# LocalR1_0.net
KiCad netlist of a schematic drawn in EAGLE
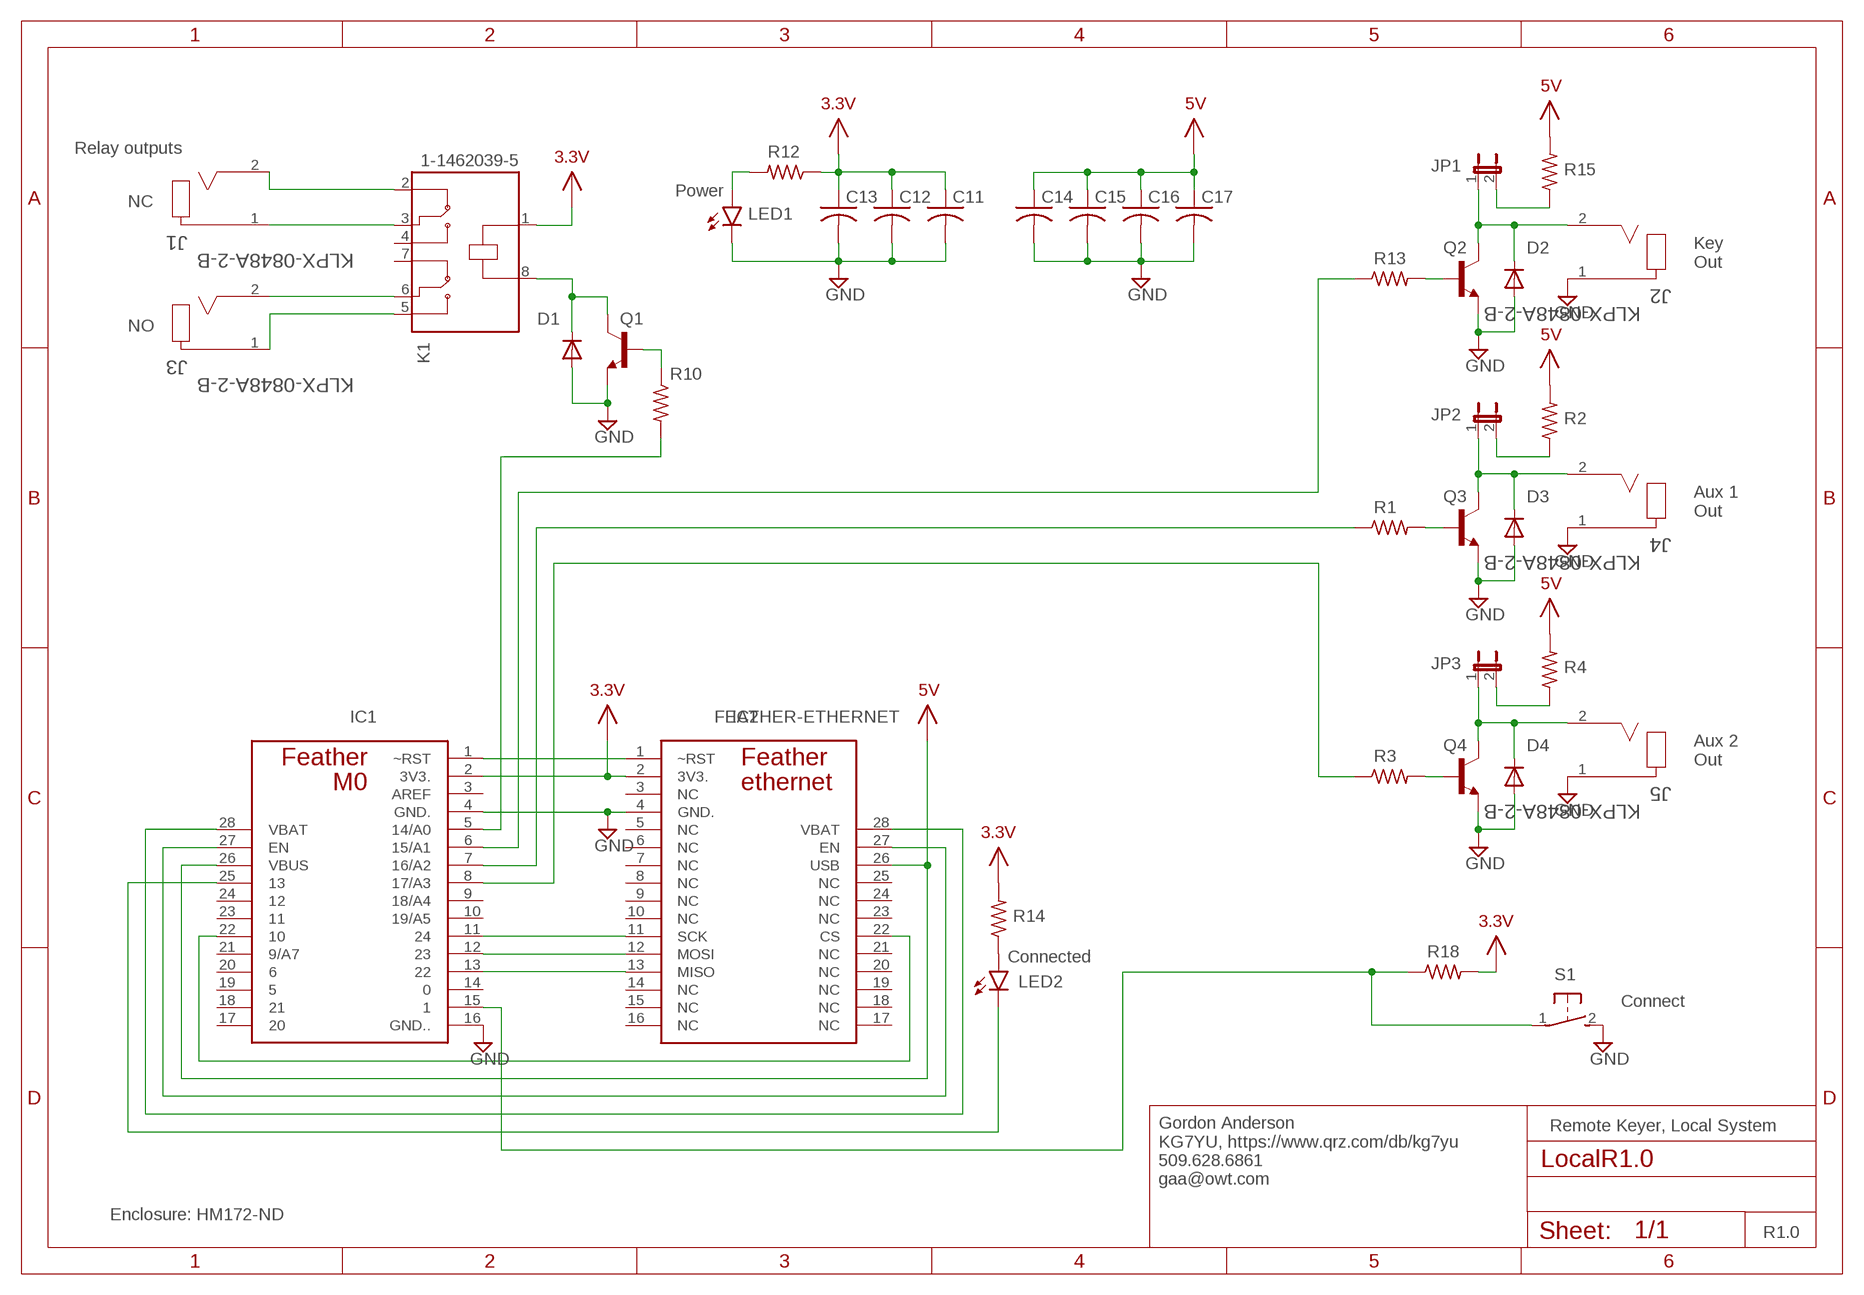
[diagram p0: schematic, sheet 1]

(export (version "E")
  (design (tool "Eeschema 10.0.6"))
  (components
    (comp (ref "C11")
      (value "C-USC0805")
      (footprint "eagle-import:C0805")
      (libsource (lib "eagle-import") (part "C-USC0805"))
    )
    (comp (ref "C12")
      (value "C-USC0805")
      (footprint "eagle-import:C0805")
      (libsource (lib "eagle-import") (part "C-USC0805"))
    )
    (comp (ref "C13")
      (value "C-USC0805")
      (footprint "eagle-import:C0805")
      (libsource (lib "eagle-import") (part "C-USC0805"))
    )
    (comp (ref "C14")
      (value "C-USC0805")
      (footprint "eagle-import:C0805")
      (libsource (lib "eagle-import") (part "C-USC0805"))
    )
    (comp (ref "C15")
      (value "C-USC0805")
      (footprint "eagle-import:C0805")
      (libsource (lib "eagle-import") (part "C-USC0805"))
    )
    (comp (ref "C16")
      (value "C-USC0805")
      (footprint "eagle-import:C0805")
      (libsource (lib "eagle-import") (part "C-USC0805"))
    )
    (comp (ref "C17")
      (value "C-USC0805")
      (footprint "eagle-import:C0805")
      (libsource (lib "eagle-import") (part "C-USC0805"))
    )
    (comp (ref "D1")
      (value "DIODE-SOD323-R")
      (footprint "eagle-import:SOD323-R")
      (libsource (lib "eagle-import") (part "DIODE-SOD323-R"))
    )
    (comp (ref "D2")
      (value "DIODE-SOD323-R")
      (footprint "eagle-import:SOD323-R")
      (libsource (lib "eagle-import") (part "DIODE-SOD323-R"))
    )
    (comp (ref "D3")
      (value "DIODE-SOD323-R")
      (footprint "eagle-import:SOD323-R")
      (libsource (lib "eagle-import") (part "DIODE-SOD323-R"))
    )
    (comp (ref "D4")
      (value "DIODE-SOD323-R")
      (footprint "eagle-import:SOD323-R")
      (libsource (lib "eagle-import") (part "DIODE-SOD323-R"))
    )
    (comp (ref "IC1")
      (value "FEATHER-M0")
      (footprint "eagle-import:FEATHER-M0")
      (libsource (lib "eagle-import") (part "FEATHER-M0"))
    )
    (comp (ref "IC2")
      (value "FEATHER-ETHERNET")
      (footprint "eagle-import:FEATHER-ETHERNET")
      (libsource (lib "eagle-import") (part "FEATHER-ETHERNET"))
    )
    (comp (ref "J1")
      (value "KLPX-0848A-2-B")
      (footprint "eagle-import:KLPX-0848A-2-B_KYC")
      (fields (field (name "COPYRIGHT") "Copyright (C) 2021 Ultra Librarian. All rights reserved."))
      (libsource (lib "eagle-import") (part "KLPX-0848A-2-B"))
    )
    (comp (ref "J2")
      (value "KLPX-0848A-2-B")
      (footprint "eagle-import:KLPX-0848A-2-B_KYC")
      (fields (field (name "COPYRIGHT") "Copyright (C) 2021 Ultra Librarian. All rights reserved."))
      (libsource (lib "eagle-import") (part "KLPX-0848A-2-B"))
    )
    (comp (ref "J3")
      (value "KLPX-0848A-2-B")
      (footprint "eagle-import:KLPX-0848A-2-B_KYC")
      (fields (field (name "COPYRIGHT") "Copyright (C) 2021 Ultra Librarian. All rights reserved."))
      (libsource (lib "eagle-import") (part "KLPX-0848A-2-B"))
    )
    (comp (ref "J4")
      (value "KLPX-0848A-2-B")
      (footprint "eagle-import:KLPX-0848A-2-B_KYC")
      (fields (field (name "COPYRIGHT") "Copyright (C) 2021 Ultra Librarian. All rights reserved."))
      (libsource (lib "eagle-import") (part "KLPX-0848A-2-B"))
    )
    (comp (ref "J5")
      (value "KLPX-0848A-2-B")
      (footprint "eagle-import:KLPX-0848A-2-B_KYC")
      (fields (field (name "COPYRIGHT") "Copyright (C) 2021 Ultra Librarian. All rights reserved."))
      (libsource (lib "eagle-import") (part "KLPX-0848A-2-B"))
    )
    (comp (ref "JP1")
      (value "JP1E")
      (footprint "eagle-import:JP1")
      (libsource (lib "eagle-import") (part "JP1E"))
    )
    (comp (ref "JP2")
      (value "JP1E")
      (footprint "eagle-import:JP1")
      (libsource (lib "eagle-import") (part "JP1E"))
    )
    (comp (ref "JP3")
      (value "JP1E")
      (footprint "eagle-import:JP1")
      (libsource (lib "eagle-import") (part "JP1E"))
    )
    (comp (ref "K1")
      (value "1-1462039-5")
      (footprint "eagle-import:RELAY_1-1462039-5")
      (fields (field (name "DIGI-KEY_PART_NUMBER") "PB1167-ND") (field (name "MF") "TE Connectivity"))
      (libsource (lib "eagle-import") (part "1-1462039-5"))
    )
    (comp (ref "LED1")
      (value "LED5MM")
      (footprint "eagle-import:LED5MM")
      (libsource (lib "eagle-import") (part "LED5MM"))
    )
    (comp (ref "LED2")
      (value "LED5MM")
      (footprint "eagle-import:LED5MM")
      (libsource (lib "eagle-import") (part "LED5MM"))
    )
    (comp (ref "Q1")
      (value "MMBT2369LT1-NPN-SOT23-BEC")
      (footprint "eagle-import:SOT23-BEC")
      (libsource (lib "eagle-import") (part "-NPN-SOT23-BECMMBT2369LT1"))
    )
    (comp (ref "Q2")
      (value "MMBT2369LT1-NPN-SOT23-BEC")
      (footprint "eagle-import:SOT23-BEC")
      (libsource (lib "eagle-import") (part "-NPN-SOT23-BECMMBT2369LT1"))
    )
    (comp (ref "Q3")
      (value "MMBT2369LT1-NPN-SOT23-BEC")
      (footprint "eagle-import:SOT23-BEC")
      (libsource (lib "eagle-import") (part "-NPN-SOT23-BECMMBT2369LT1"))
    )
    (comp (ref "Q4")
      (value "MMBT2369LT1-NPN-SOT23-BEC")
      (footprint "eagle-import:SOT23-BEC")
      (libsource (lib "eagle-import") (part "-NPN-SOT23-BECMMBT2369LT1"))
    )
    (comp (ref "R1")
      (value "R-US_R0805")
      (footprint "eagle-import:R0805")
      (libsource (lib "eagle-import") (part "R-US_R0805"))
    )
    (comp (ref "R2")
      (value "R-US_R0805")
      (footprint "eagle-import:R0805")
      (libsource (lib "eagle-import") (part "R-US_R0805"))
    )
    (comp (ref "R3")
      (value "R-US_R0805")
      (footprint "eagle-import:R0805")
      (libsource (lib "eagle-import") (part "R-US_R0805"))
    )
    (comp (ref "R4")
      (value "R-US_R0805")
      (footprint "eagle-import:R0805")
      (libsource (lib "eagle-import") (part "R-US_R0805"))
    )
    (comp (ref "R10")
      (value "R-US_R0805")
      (footprint "eagle-import:R0805")
      (libsource (lib "eagle-import") (part "R-US_R0805"))
    )
    (comp (ref "R12")
      (value "R-US_R0805")
      (footprint "eagle-import:R0805")
      (libsource (lib "eagle-import") (part "R-US_R0805"))
    )
    (comp (ref "R13")
      (value "R-US_R0805")
      (footprint "eagle-import:R0805")
      (libsource (lib "eagle-import") (part "R-US_R0805"))
    )
    (comp (ref "R14")
      (value "R-US_R0805")
      (footprint "eagle-import:R0805")
      (libsource (lib "eagle-import") (part "R-US_R0805"))
    )
    (comp (ref "R15")
      (value "R-US_R0805")
      (footprint "eagle-import:R0805")
      (libsource (lib "eagle-import") (part "R-US_R0805"))
    )
    (comp (ref "R18")
      (value "R-US_R0805")
      (footprint "eagle-import:R0805")
      (libsource (lib "eagle-import") (part "R-US_R0805"))
    )
    (comp (ref "S1")
      (value "31-XX")
      (footprint "eagle-import:B3F-31XX")
      (fields (field (name "MPN") "B3F-3100"))
      (libsource (lib "eagle-import") (part "31-XX"))
    )
  )
  (nets
    (net (code "1") (name "/NC") (class "Default")
      (node (ref "IC2") (pin "16") (pinfunction "NC_16") (pintype "power_in"))
    )
    (net (code "2") (name "3.3V") (class "Default")
      (node (ref "C11") (pin "1") (pinfunction "1_1") (pintype "passive"))
      (node (ref "C12") (pin "1") (pinfunction "1_1") (pintype "passive"))
      (node (ref "C13") (pin "1") (pinfunction "1_1") (pintype "passive"))
      (node (ref "IC1") (pin "2") (pinfunction "3V3._2") (pintype "power_in"))
      (node (ref "IC2") (pin "2") (pinfunction "3V3._2") (pintype "power_in"))
      (node (ref "K1") (pin "1") (pinfunction "1_1") (pintype "passive"))
      (node (ref "R12") (pin "1") (pinfunction "1_1") (pintype "passive"))
      (node (ref "R14") (pin "2") (pinfunction "2_2") (pintype "passive"))
      (node (ref "R18") (pin "2") (pinfunction "2_2") (pintype "passive"))
    )
    (net (code "3") (name "5V") (class "Default")
      (node (ref "C14") (pin "1") (pinfunction "1_1") (pintype "passive"))
      (node (ref "C15") (pin "1") (pinfunction "1_1") (pintype "passive"))
      (node (ref "C16") (pin "1") (pinfunction "1_1") (pintype "passive"))
      (node (ref "C17") (pin "1") (pinfunction "1_1") (pintype "passive"))
      (node (ref "IC1") (pin "26") (pinfunction "VBUS_26") (pintype "power_in"))
      (node (ref "IC2") (pin "26") (pinfunction "USB_26") (pintype "power_in"))
      (node (ref "R15") (pin "2") (pinfunction "2_2") (pintype "passive"))
      (node (ref "R2") (pin "2") (pinfunction "2_2") (pintype "passive"))
      (node (ref "R4") (pin "2") (pinfunction "2_2") (pintype "passive"))
    )
    (net (code "4") (name "GND") (class "Default")
      (node (ref "C11") (pin "2") (pinfunction "2_2") (pintype "passive"))
      (node (ref "C12") (pin "2") (pinfunction "2_2") (pintype "passive"))
      (node (ref "C13") (pin "2") (pinfunction "2_2") (pintype "passive"))
      (node (ref "C14") (pin "2") (pinfunction "2_2") (pintype "passive"))
      (node (ref "C15") (pin "2") (pinfunction "2_2") (pintype "passive"))
      (node (ref "C16") (pin "2") (pinfunction "2_2") (pintype "passive"))
      (node (ref "C17") (pin "2") (pinfunction "2_2") (pintype "passive"))
      (node (ref "D1") (pin "A") (pinfunction "A_A") (pintype "passive"))
      (node (ref "D2") (pin "A") (pinfunction "A_A") (pintype "passive"))
      (node (ref "D3") (pin "A") (pinfunction "A_A") (pintype "passive"))
      (node (ref "D4") (pin "A") (pinfunction "A_A") (pintype "passive"))
      (node (ref "IC1") (pin "16") (pinfunction "GND.._16") (pintype "power_in"))
      (node (ref "IC1") (pin "4") (pinfunction "GND._4") (pintype "power_in"))
      (node (ref "IC2") (pin "4") (pinfunction "GND._4") (pintype "power_in"))
      (node (ref "J2") (pin "1") (pinfunction "1_1") (pintype "passive"))
      (node (ref "J4") (pin "1") (pinfunction "1_1") (pintype "passive"))
      (node (ref "J5") (pin "1") (pinfunction "1_1") (pintype "passive"))
      (node (ref "LED1") (pin "K") (pinfunction "C_K") (pintype "passive"))
      (node (ref "Q1") (pin "E") (pinfunction "E_E") (pintype "passive"))
      (node (ref "Q2") (pin "E") (pinfunction "E_E") (pintype "passive"))
      (node (ref "Q3") (pin "E") (pinfunction "E_E") (pintype "passive"))
      (node (ref "Q4") (pin "E") (pinfunction "E_E") (pintype "passive"))
      (node (ref "S1") (pin "2") (pinfunction "S_2") (pintype "passive"))
    )
    (net (code "5") (name "Net-(D1-PadC)") (class "Default")
      (node (ref "D1") (pin "C") (pinfunction "C_C") (pintype "passive"))
      (node (ref "K1") (pin "8") (pinfunction "8_8") (pintype "passive"))
      (node (ref "Q1") (pin "C") (pinfunction "C_C") (pintype "passive"))
    )
    (net (code "6") (name "Net-(D2-PadC)") (class "Default")
      (node (ref "D2") (pin "C") (pinfunction "C_C") (pintype "passive"))
      (node (ref "J2") (pin "2") (pinfunction "2_2") (pintype "passive"))
      (node (ref "JP1") (pin "1") (pinfunction "1_1") (pintype "passive"))
      (node (ref "Q2") (pin "C") (pinfunction "C_C") (pintype "passive"))
    )
    (net (code "7") (name "Net-(D3-PadC)") (class "Default")
      (node (ref "D3") (pin "C") (pinfunction "C_C") (pintype "passive"))
      (node (ref "J4") (pin "2") (pinfunction "2_2") (pintype "passive"))
      (node (ref "JP2") (pin "1") (pinfunction "1_1") (pintype "passive"))
      (node (ref "Q3") (pin "C") (pinfunction "C_C") (pintype "passive"))
    )
    (net (code "8") (name "Net-(D4-PadC)") (class "Default")
      (node (ref "D4") (pin "C") (pinfunction "C_C") (pintype "passive"))
      (node (ref "J5") (pin "2") (pinfunction "2_2") (pintype "passive"))
      (node (ref "JP3") (pin "1") (pinfunction "1_1") (pintype "passive"))
      (node (ref "Q4") (pin "C") (pinfunction "C_C") (pintype "passive"))
    )
    (net (code "9") (name "Net-(IC1-1)") (class "Default")
      (node (ref "IC1") (pin "15") (pinfunction "1_15") (pintype "bidirectional"))
      (node (ref "R18") (pin "1") (pinfunction "1_1") (pintype "passive"))
      (node (ref "S1") (pin "1") (pinfunction "P_1") (pintype "passive"))
    )
    (net (code "10") (name "Net-(IC1-10)") (class "Default")
      (node (ref "IC1") (pin "22") (pinfunction "10_22") (pintype "bidirectional"))
      (node (ref "IC2") (pin "22") (pinfunction "CS_22") (pintype "bidirectional"))
    )
    (net (code "11") (name "Net-(IC1-13)") (class "Default")
      (node (ref "IC1") (pin "25") (pinfunction "13_25") (pintype "bidirectional"))
      (node (ref "LED2") (pin "K") (pinfunction "C_K") (pintype "passive"))
    )
    (net (code "12") (name "Net-(IC1-14{slash}A0)") (class "Default")
      (node (ref "IC1") (pin "5") (pinfunction "14/A0_5") (pintype "bidirectional"))
      (node (ref "R10") (pin "2") (pinfunction "2_2") (pintype "passive"))
    )
    (net (code "13") (name "Net-(IC1-15{slash}A1)") (class "Default")
      (node (ref "IC1") (pin "6") (pinfunction "15/A1_6") (pintype "bidirectional"))
      (node (ref "R13") (pin "1") (pinfunction "1_1") (pintype "passive"))
    )
    (net (code "14") (name "Net-(IC1-16{slash}A2)") (class "Default")
      (node (ref "IC1") (pin "7") (pinfunction "16/A2_7") (pintype "bidirectional"))
      (node (ref "R1") (pin "1") (pinfunction "1_1") (pintype "passive"))
    )
    (net (code "15") (name "Net-(IC1-17{slash}A3)") (class "Default")
      (node (ref "IC1") (pin "8") (pinfunction "17/A3_8") (pintype "bidirectional"))
      (node (ref "R3") (pin "1") (pinfunction "1_1") (pintype "passive"))
    )
    (net (code "16") (name "Net-(IC1-22)") (class "Default")
      (node (ref "IC1") (pin "13") (pinfunction "22_13") (pintype "bidirectional"))
      (node (ref "IC2") (pin "13") (pinfunction "MISO_13") (pintype "bidirectional"))
    )
    (net (code "17") (name "Net-(IC1-23)") (class "Default")
      (node (ref "IC1") (pin "12") (pinfunction "23_12") (pintype "bidirectional"))
      (node (ref "IC2") (pin "12") (pinfunction "MOSI_12") (pintype "bidirectional"))
    )
    (net (code "18") (name "Net-(IC1-24)") (class "Default")
      (node (ref "IC1") (pin "11") (pinfunction "24_11") (pintype "bidirectional"))
      (node (ref "IC2") (pin "11") (pinfunction "SCK_11") (pintype "bidirectional"))
    )
    (net (code "19") (name "Net-(IC1-EN)") (class "Default")
      (node (ref "IC1") (pin "27") (pinfunction "EN_27") (pintype "input"))
      (node (ref "IC2") (pin "27") (pinfunction "EN_27") (pintype "input"))
    )
    (net (code "20") (name "Net-(IC1-VBAT)") (class "Default")
      (node (ref "IC1") (pin "28") (pinfunction "VBAT_28") (pintype "power_in"))
      (node (ref "IC2") (pin "28") (pinfunction "VBAT_28") (pintype "power_in"))
    )
    (net (code "21") (name "Net-(IC1-~{RST})") (class "Default")
      (node (ref "IC1") (pin "1") (pinfunction "~{RST}_1") (pintype "input"))
      (node (ref "IC2") (pin "1") (pinfunction "~{RST}_1") (pintype "input"))
    )
    (net (code "22") (name "Net-(J1-Pad1)") (class "Default")
      (node (ref "J1") (pin "1") (pinfunction "1_1") (pintype "passive"))
      (node (ref "K1") (pin "3") (pinfunction "3_3") (pintype "passive"))
    )
    (net (code "23") (name "Net-(J1-Pad2)") (class "Default")
      (node (ref "J1") (pin "2") (pinfunction "2_2") (pintype "passive"))
      (node (ref "K1") (pin "2") (pinfunction "2_2") (pintype "passive"))
    )
    (net (code "24") (name "Net-(J3-Pad1)") (class "Default")
      (node (ref "J3") (pin "1") (pinfunction "1_1") (pintype "passive"))
      (node (ref "K1") (pin "5") (pinfunction "5_5") (pintype "passive"))
    )
    (net (code "25") (name "Net-(J3-Pad2)") (class "Default")
      (node (ref "J3") (pin "2") (pinfunction "2_2") (pintype "passive"))
      (node (ref "K1") (pin "6") (pinfunction "6_6") (pintype "passive"))
    )
    (net (code "26") (name "Net-(JP1-Pad2)") (class "Default")
      (node (ref "JP1") (pin "2") (pinfunction "2_2") (pintype "passive"))
      (node (ref "R15") (pin "1") (pinfunction "1_1") (pintype "passive"))
    )
    (net (code "27") (name "Net-(JP2-Pad2)") (class "Default")
      (node (ref "JP2") (pin "2") (pinfunction "2_2") (pintype "passive"))
      (node (ref "R2") (pin "1") (pinfunction "1_1") (pintype "passive"))
    )
    (net (code "28") (name "Net-(JP3-Pad2)") (class "Default")
      (node (ref "JP3") (pin "2") (pinfunction "2_2") (pintype "passive"))
      (node (ref "R4") (pin "1") (pinfunction "1_1") (pintype "passive"))
    )
    (net (code "29") (name "Net-(LED1-PadA)") (class "Default")
      (node (ref "LED1") (pin "A") (pinfunction "A_A") (pintype "passive"))
      (node (ref "R12") (pin "2") (pinfunction "2_2") (pintype "passive"))
    )
    (net (code "30") (name "Net-(LED2-PadA)") (class "Default")
      (node (ref "LED2") (pin "A") (pinfunction "A_A") (pintype "passive"))
      (node (ref "R14") (pin "1") (pinfunction "1_1") (pintype "passive"))
    )
    (net (code "31") (name "Net-(Q1-PadB)") (class "Default")
      (node (ref "Q1") (pin "B") (pinfunction "B_B") (pintype "passive"))
      (node (ref "R10") (pin "1") (pinfunction "1_1") (pintype "passive"))
    )
    (net (code "32") (name "Net-(Q2-PadB)") (class "Default")
      (node (ref "Q2") (pin "B") (pinfunction "B_B") (pintype "passive"))
      (node (ref "R13") (pin "2") (pinfunction "2_2") (pintype "passive"))
    )
    (net (code "33") (name "Net-(Q3-PadB)") (class "Default")
      (node (ref "Q3") (pin "B") (pinfunction "B_B") (pintype "passive"))
      (node (ref "R1") (pin "2") (pinfunction "2_2") (pintype "passive"))
    )
    (net (code "34") (name "Net-(Q4-PadB)") (class "Default")
      (node (ref "Q4") (pin "B") (pinfunction "B_B") (pintype "passive"))
      (node (ref "R3") (pin "2") (pinfunction "2_2") (pintype "passive"))
    )
    (net (code "35") (name "unconnected-(IC1-0-Pad14)") (class "Default")
      (node (ref "IC1") (pin "14") (pinfunction "0_14") (pintype "bidirectional"))
    )
    (net (code "36") (name "unconnected-(IC1-5-Pad19)") (class "Default")
      (node (ref "IC1") (pin "19") (pinfunction "5_19") (pintype "bidirectional"))
    )
    (net (code "37") (name "unconnected-(IC1-6-Pad20)") (class "Default")
      (node (ref "IC1") (pin "20") (pinfunction "6_20") (pintype "bidirectional"))
    )
    (net (code "38") (name "unconnected-(IC1-9{slash}A7-Pad21)") (class "Default")
      (node (ref "IC1") (pin "21") (pinfunction "9/A7_21") (pintype "bidirectional"))
    )
    (net (code "39") (name "unconnected-(IC1-11-Pad23)") (class "Default")
      (node (ref "IC1") (pin "23") (pinfunction "11_23") (pintype "bidirectional"))
    )
    (net (code "40") (name "unconnected-(IC1-12-Pad24)") (class "Default")
      (node (ref "IC1") (pin "24") (pinfunction "12_24") (pintype "bidirectional"))
    )
    (net (code "41") (name "unconnected-(IC1-18{slash}A4-Pad9)") (class "Default")
      (node (ref "IC1") (pin "9") (pinfunction "18/A4_9") (pintype "bidirectional"))
    )
    (net (code "42") (name "unconnected-(IC1-19{slash}A5-Pad10)") (class "Default")
      (node (ref "IC1") (pin "10") (pinfunction "19/A5_10") (pintype "bidirectional"))
    )
    (net (code "43") (name "unconnected-(IC1-20-Pad17)") (class "Default")
      (node (ref "IC1") (pin "17") (pinfunction "20_17") (pintype "bidirectional"))
    )
    (net (code "44") (name "unconnected-(IC1-21-Pad18)") (class "Default")
      (node (ref "IC1") (pin "18") (pinfunction "21_18") (pintype "bidirectional"))
    )
    (net (code "45") (name "unconnected-(IC1-AREF-Pad3)") (class "Default")
      (node (ref "IC1") (pin "3") (pinfunction "AREF_3") (pintype "input"))
    )
    (net (code "46") (name "unconnected-(IC2-NC-Pad3)") (class "Default")
      (node (ref "IC2") (pin "3") (pinfunction "NC_3") (pintype "input"))
    )
    (net (code "47") (name "unconnected-(IC2-NC-Pad5)") (class "Default")
      (node (ref "IC2") (pin "5") (pinfunction "NC_5") (pintype "bidirectional"))
    )
    (net (code "48") (name "unconnected-(IC2-NC-Pad6)") (class "Default")
      (node (ref "IC2") (pin "6") (pinfunction "NC_6") (pintype "bidirectional"))
    )
    (net (code "49") (name "unconnected-(IC2-NC-Pad7)") (class "Default")
      (node (ref "IC2") (pin "7") (pinfunction "NC_7") (pintype "bidirectional"))
    )
    (net (code "50") (name "unconnected-(IC2-NC-Pad8)") (class "Default")
      (node (ref "IC2") (pin "8") (pinfunction "NC_8") (pintype "bidirectional"))
    )
    (net (code "51") (name "unconnected-(IC2-NC-Pad9)") (class "Default")
      (node (ref "IC2") (pin "9") (pinfunction "NC_9") (pintype "bidirectional"))
    )
    (net (code "52") (name "unconnected-(IC2-NC-Pad10)") (class "Default")
      (node (ref "IC2") (pin "10") (pinfunction "NC_10") (pintype "bidirectional"))
    )
    (net (code "53") (name "unconnected-(IC2-NC-Pad14)") (class "Default")
      (node (ref "IC2") (pin "14") (pinfunction "NC_14") (pintype "bidirectional"))
    )
    (net (code "54") (name "unconnected-(IC2-NC-Pad15)") (class "Default")
      (node (ref "IC2") (pin "15") (pinfunction "NC_15") (pintype "bidirectional"))
    )
    (net (code "55") (name "unconnected-(IC2-NC-Pad17)") (class "Default")
      (node (ref "IC2") (pin "17") (pinfunction "NC_17") (pintype "bidirectional"))
    )
    (net (code "56") (name "unconnected-(IC2-NC-Pad18)") (class "Default")
      (node (ref "IC2") (pin "18") (pinfunction "NC_18") (pintype "bidirectional"))
    )
    (net (code "57") (name "unconnected-(IC2-NC-Pad19)") (class "Default")
      (node (ref "IC2") (pin "19") (pinfunction "NC_19") (pintype "bidirectional"))
    )
    (net (code "58") (name "unconnected-(IC2-NC-Pad20)") (class "Default")
      (node (ref "IC2") (pin "20") (pinfunction "NC_20") (pintype "bidirectional"))
    )
    (net (code "59") (name "unconnected-(IC2-NC-Pad21)") (class "Default")
      (node (ref "IC2") (pin "21") (pinfunction "NC_21") (pintype "bidirectional"))
    )
    (net (code "60") (name "unconnected-(IC2-NC-Pad23)") (class "Default")
      (node (ref "IC2") (pin "23") (pinfunction "NC_23") (pintype "bidirectional"))
    )
    (net (code "61") (name "unconnected-(IC2-NC-Pad24)") (class "Default")
      (node (ref "IC2") (pin "24") (pinfunction "NC_24") (pintype "bidirectional"))
    )
    (net (code "62") (name "unconnected-(IC2-NC-Pad25)") (class "Default")
      (node (ref "IC2") (pin "25") (pinfunction "NC_25") (pintype "bidirectional"))
    )
    (net (code "63") (name "unconnected-(K1-Pad4)") (class "Default")
      (node (ref "K1") (pin "4") (pinfunction "4_4") (pintype "passive"))
    )
    (net (code "64") (name "unconnected-(K1-Pad7)") (class "Default")
      (node (ref "K1") (pin "7") (pinfunction "7_7") (pintype "passive"))
    )
  )
)
